# NumPad.net
KiCad netlist of a schematic drawn in EAGLE
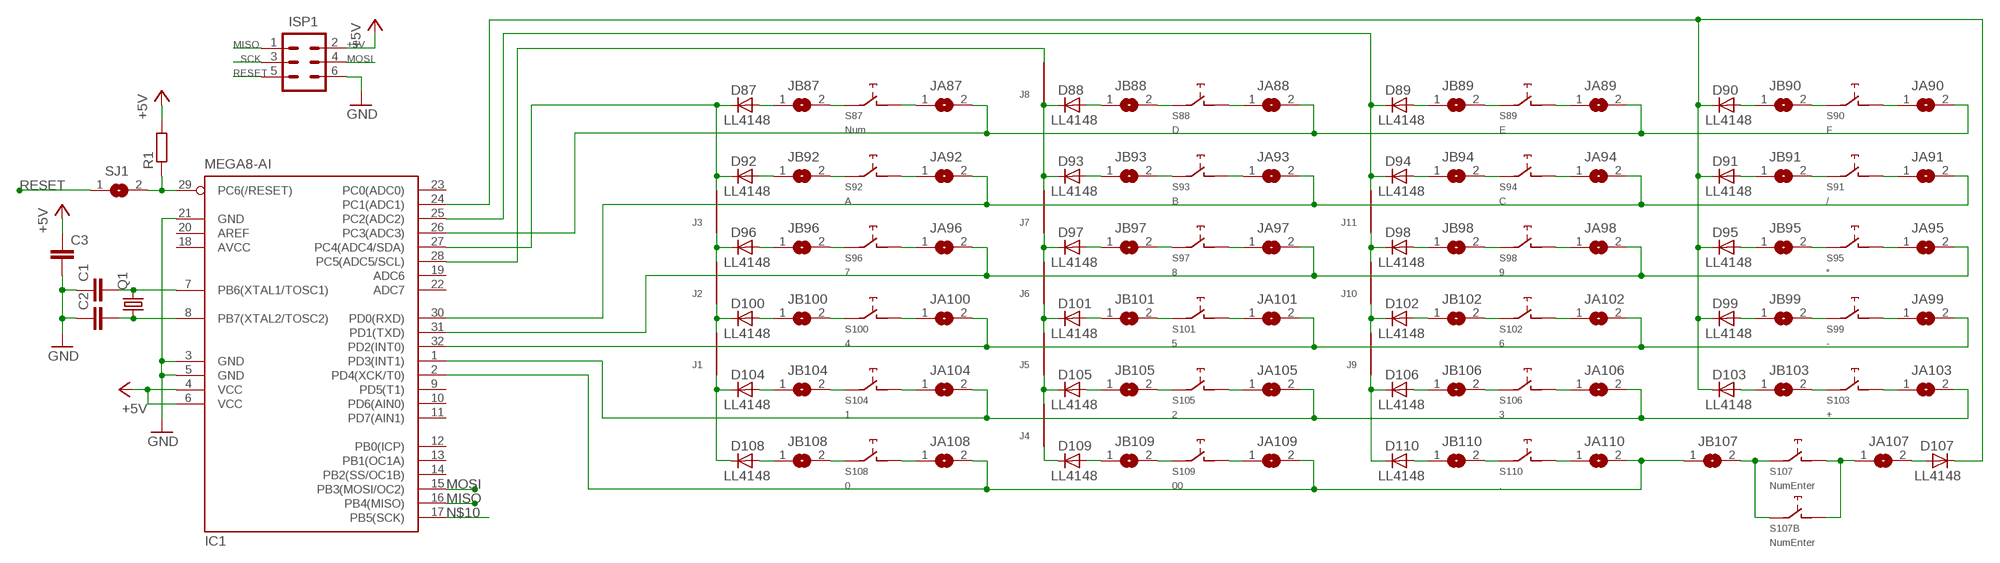
[diagram p0: schematic, sheet 1]

(export (version "E")
  (design (tool "Eeschema 10.0.6"))
  (components
    (comp (ref "C1")
      (value "C-EUC0805")
      (footprint "eagle-import:C0805")
      (libsource (lib "eagle-import") (part "C-EUC0805"))
    )
    (comp (ref "C2")
      (value "C-EUC0805")
      (footprint "eagle-import:C0805")
      (libsource (lib "eagle-import") (part "C-EUC0805"))
    )
    (comp (ref "C3")
      (value "C-EUC0805")
      (footprint "eagle-import:C0805")
      (libsource (lib "eagle-import") (part "C-EUC0805"))
    )
    (comp (ref "D87")
      (value "LL4148")
      (footprint "eagle-import:SOD80C")
      (libsource (lib "eagle-import") (part "LL4148"))
    )
    (comp (ref "D88")
      (value "LL4148")
      (footprint "eagle-import:SOD80C")
      (libsource (lib "eagle-import") (part "LL4148"))
    )
    (comp (ref "D89")
      (value "LL4148")
      (footprint "eagle-import:SOD80C")
      (libsource (lib "eagle-import") (part "LL4148"))
    )
    (comp (ref "D90")
      (value "LL4148")
      (footprint "eagle-import:SOD80C")
      (libsource (lib "eagle-import") (part "LL4148"))
    )
    (comp (ref "D91")
      (value "LL4148")
      (footprint "eagle-import:SOD80C")
      (libsource (lib "eagle-import") (part "LL4148"))
    )
    (comp (ref "D92")
      (value "LL4148")
      (footprint "eagle-import:SOD80C")
      (libsource (lib "eagle-import") (part "LL4148"))
    )
    (comp (ref "D93")
      (value "LL4148")
      (footprint "eagle-import:SOD80C")
      (libsource (lib "eagle-import") (part "LL4148"))
    )
    (comp (ref "D94")
      (value "LL4148")
      (footprint "eagle-import:SOD80C")
      (libsource (lib "eagle-import") (part "LL4148"))
    )
    (comp (ref "D95")
      (value "LL4148")
      (footprint "eagle-import:SOD80C")
      (libsource (lib "eagle-import") (part "LL4148"))
    )
    (comp (ref "D96")
      (value "LL4148")
      (footprint "eagle-import:SOD80C")
      (libsource (lib "eagle-import") (part "LL4148"))
    )
    (comp (ref "D97")
      (value "LL4148")
      (footprint "eagle-import:SOD80C")
      (libsource (lib "eagle-import") (part "LL4148"))
    )
    (comp (ref "D98")
      (value "LL4148")
      (footprint "eagle-import:SOD80C")
      (libsource (lib "eagle-import") (part "LL4148"))
    )
    (comp (ref "D99")
      (value "LL4148")
      (footprint "eagle-import:SOD80C")
      (libsource (lib "eagle-import") (part "LL4148"))
    )
    (comp (ref "D100")
      (value "LL4148")
      (footprint "eagle-import:SOD80C")
      (libsource (lib "eagle-import") (part "LL4148"))
    )
    (comp (ref "D101")
      (value "LL4148")
      (footprint "eagle-import:SOD80C")
      (libsource (lib "eagle-import") (part "LL4148"))
    )
    (comp (ref "D102")
      (value "LL4148")
      (footprint "eagle-import:SOD80C")
      (libsource (lib "eagle-import") (part "LL4148"))
    )
    (comp (ref "D103")
      (value "LL4148")
      (footprint "eagle-import:SOD80C")
      (libsource (lib "eagle-import") (part "LL4148"))
    )
    (comp (ref "D104")
      (value "LL4148")
      (footprint "eagle-import:SOD80C")
      (libsource (lib "eagle-import") (part "LL4148"))
    )
    (comp (ref "D105")
      (value "LL4148")
      (footprint "eagle-import:SOD80C")
      (libsource (lib "eagle-import") (part "LL4148"))
    )
    (comp (ref "D106")
      (value "LL4148")
      (footprint "eagle-import:SOD80C")
      (libsource (lib "eagle-import") (part "LL4148"))
    )
    (comp (ref "D107")
      (value "LL4148")
      (footprint "eagle-import:SOD80C")
      (libsource (lib "eagle-import") (part "LL4148"))
    )
    (comp (ref "D108")
      (value "LL4148")
      (footprint "eagle-import:SOD80C")
      (libsource (lib "eagle-import") (part "LL4148"))
    )
    (comp (ref "D109")
      (value "LL4148")
      (footprint "eagle-import:SOD80C")
      (libsource (lib "eagle-import") (part "LL4148"))
    )
    (comp (ref "D110")
      (value "LL4148")
      (footprint "eagle-import:SOD80C")
      (libsource (lib "eagle-import") (part "LL4148"))
    )
    (comp (ref "IC1")
      (value "MEGA8-AI")
      (footprint "eagle-import:TQFP32-08")
      (fields (field (name "MPN") "ATMEGA8-16AU"))
      (libsource (lib "eagle-import") (part "MEGA8-AI"))
    )
    (comp (ref "ISP1")
      (value "MA03-2")
      (footprint "eagle-import:MA03-2")
      (libsource (lib "eagle-import") (part "MA03-2"))
    )
    (comp (ref "J1")
      (value "J")
      (footprint "eagle-import:R1206W")
      (libsource (lib "eagle-import") (part "J"))
    )
    (comp (ref "J2")
      (value "J")
      (footprint "eagle-import:R1206W")
      (libsource (lib "eagle-import") (part "J"))
    )
    (comp (ref "J3")
      (value "J")
      (footprint "eagle-import:R1206W")
      (libsource (lib "eagle-import") (part "J"))
    )
    (comp (ref "J4")
      (value "J")
      (footprint "eagle-import:R1206W")
      (libsource (lib "eagle-import") (part "J"))
    )
    (comp (ref "J5")
      (value "J")
      (footprint "eagle-import:R1206W")
      (libsource (lib "eagle-import") (part "J"))
    )
    (comp (ref "J6")
      (value "J")
      (footprint "eagle-import:R1206W")
      (libsource (lib "eagle-import") (part "J"))
    )
    (comp (ref "J7")
      (value "J")
      (footprint "eagle-import:R1206W")
      (libsource (lib "eagle-import") (part "J"))
    )
    (comp (ref "J8")
      (value "J")
      (footprint "eagle-import:R1206W")
      (libsource (lib "eagle-import") (part "J"))
    )
    (comp (ref "J9")
      (value "J")
      (footprint "eagle-import:R1206W")
      (libsource (lib "eagle-import") (part "J"))
    )
    (comp (ref "J10")
      (value "J")
      (footprint "eagle-import:R1206W")
      (libsource (lib "eagle-import") (part "J"))
    )
    (comp (ref "J11")
      (value "J")
      (footprint "eagle-import:R1206W")
      (libsource (lib "eagle-import") (part "J"))
    )
    (comp (ref "JA87")
      (value "SJ")
      (footprint "eagle-import:SJ")
      (libsource (lib "eagle-import") (part "SJ"))
    )
    (comp (ref "JA88")
      (value "SJ")
      (footprint "eagle-import:SJ")
      (libsource (lib "eagle-import") (part "SJ"))
    )
    (comp (ref "JA89")
      (value "SJ")
      (footprint "eagle-import:SJ")
      (libsource (lib "eagle-import") (part "SJ"))
    )
    (comp (ref "JA90")
      (value "SJ")
      (footprint "eagle-import:SJ")
      (libsource (lib "eagle-import") (part "SJ"))
    )
    (comp (ref "JA91")
      (value "SJ")
      (footprint "eagle-import:SJ")
      (libsource (lib "eagle-import") (part "SJ"))
    )
    (comp (ref "JA92")
      (value "SJ")
      (footprint "eagle-import:SJ")
      (libsource (lib "eagle-import") (part "SJ"))
    )
    (comp (ref "JA93")
      (value "SJ")
      (footprint "eagle-import:SJ")
      (libsource (lib "eagle-import") (part "SJ"))
    )
    (comp (ref "JA94")
      (value "SJ")
      (footprint "eagle-import:SJ")
      (libsource (lib "eagle-import") (part "SJ"))
    )
    (comp (ref "JA95")
      (value "SJ")
      (footprint "eagle-import:SJ")
      (libsource (lib "eagle-import") (part "SJ"))
    )
    (comp (ref "JA96")
      (value "SJ")
      (footprint "eagle-import:SJ")
      (libsource (lib "eagle-import") (part "SJ"))
    )
    (comp (ref "JA97")
      (value "SJ")
      (footprint "eagle-import:SJ")
      (libsource (lib "eagle-import") (part "SJ"))
    )
    (comp (ref "JA98")
      (value "SJ")
      (footprint "eagle-import:SJ")
      (libsource (lib "eagle-import") (part "SJ"))
    )
    (comp (ref "JA99")
      (value "SJ")
      (footprint "eagle-import:SJ")
      (libsource (lib "eagle-import") (part "SJ"))
    )
    (comp (ref "JA100")
      (value "SJ")
      (footprint "eagle-import:SJ")
      (libsource (lib "eagle-import") (part "SJ"))
    )
    (comp (ref "JA101")
      (value "SJ")
      (footprint "eagle-import:SJ")
      (libsource (lib "eagle-import") (part "SJ"))
    )
    (comp (ref "JA102")
      (value "SJ")
      (footprint "eagle-import:SJ")
      (libsource (lib "eagle-import") (part "SJ"))
    )
    (comp (ref "JA103")
      (value "SJ")
      (footprint "eagle-import:SJ")
      (libsource (lib "eagle-import") (part "SJ"))
    )
    (comp (ref "JA104")
      (value "SJ")
      (footprint "eagle-import:SJ")
      (libsource (lib "eagle-import") (part "SJ"))
    )
    (comp (ref "JA105")
      (value "SJ")
      (footprint "eagle-import:SJ")
      (libsource (lib "eagle-import") (part "SJ"))
    )
    (comp (ref "JA106")
      (value "SJ")
      (footprint "eagle-import:SJ")
      (libsource (lib "eagle-import") (part "SJ"))
    )
    (comp (ref "JA107")
      (value "SJ")
      (footprint "eagle-import:SJ")
      (libsource (lib "eagle-import") (part "SJ"))
    )
    (comp (ref "JA108")
      (value "SJ")
      (footprint "eagle-import:SJ")
      (libsource (lib "eagle-import") (part "SJ"))
    )
    (comp (ref "JA109")
      (value "SJ")
      (footprint "eagle-import:SJ")
      (libsource (lib "eagle-import") (part "SJ"))
    )
    (comp (ref "JA110")
      (value "SJ")
      (footprint "eagle-import:SJ")
      (libsource (lib "eagle-import") (part "SJ"))
    )
    (comp (ref "JB87")
      (value "SJ")
      (footprint "eagle-import:SJ")
      (libsource (lib "eagle-import") (part "SJ"))
    )
    (comp (ref "JB88")
      (value "SJ")
      (footprint "eagle-import:SJ")
      (libsource (lib "eagle-import") (part "SJ"))
    )
    (comp (ref "JB89")
      (value "SJ")
      (footprint "eagle-import:SJ")
      (libsource (lib "eagle-import") (part "SJ"))
    )
    (comp (ref "JB90")
      (value "SJ")
      (footprint "eagle-import:SJ")
      (libsource (lib "eagle-import") (part "SJ"))
    )
    (comp (ref "JB91")
      (value "SJ")
      (footprint "eagle-import:SJ")
      (libsource (lib "eagle-import") (part "SJ"))
    )
    (comp (ref "JB92")
      (value "SJ")
      (footprint "eagle-import:SJ")
      (libsource (lib "eagle-import") (part "SJ"))
    )
    (comp (ref "JB93")
      (value "SJ")
      (footprint "eagle-import:SJ")
      (libsource (lib "eagle-import") (part "SJ"))
    )
    (comp (ref "JB94")
      (value "SJ")
      (footprint "eagle-import:SJ")
      (libsource (lib "eagle-import") (part "SJ"))
    )
    (comp (ref "JB95")
      (value "SJ")
      (footprint "eagle-import:SJ")
      (libsource (lib "eagle-import") (part "SJ"))
    )
    (comp (ref "JB96")
      (value "SJ")
      (footprint "eagle-import:SJ")
      (libsource (lib "eagle-import") (part "SJ"))
    )
    (comp (ref "JB97")
      (value "SJ")
      (footprint "eagle-import:SJ")
      (libsource (lib "eagle-import") (part "SJ"))
    )
    (comp (ref "JB98")
      (value "SJ")
      (footprint "eagle-import:SJ")
      (libsource (lib "eagle-import") (part "SJ"))
    )
    (comp (ref "JB99")
      (value "SJ")
      (footprint "eagle-import:SJ")
      (libsource (lib "eagle-import") (part "SJ"))
    )
    (comp (ref "JB100")
      (value "SJ")
      (footprint "eagle-import:SJ")
      (libsource (lib "eagle-import") (part "SJ"))
    )
    (comp (ref "JB101")
      (value "SJ")
      (footprint "eagle-import:SJ")
      (libsource (lib "eagle-import") (part "SJ"))
    )
    (comp (ref "JB102")
      (value "SJ")
      (footprint "eagle-import:SJ")
      (libsource (lib "eagle-import") (part "SJ"))
    )
    (comp (ref "JB103")
      (value "SJ")
      (footprint "eagle-import:SJ")
      (libsource (lib "eagle-import") (part "SJ"))
    )
    (comp (ref "JB104")
      (value "SJ")
      (footprint "eagle-import:SJ")
      (libsource (lib "eagle-import") (part "SJ"))
    )
    (comp (ref "JB105")
      (value "SJ")
      (footprint "eagle-import:SJ")
      (libsource (lib "eagle-import") (part "SJ"))
    )
    (comp (ref "JB106")
      (value "SJ")
      (footprint "eagle-import:SJ")
      (libsource (lib "eagle-import") (part "SJ"))
    )
    (comp (ref "JB107")
      (value "SJ")
      (footprint "eagle-import:SJ")
      (libsource (lib "eagle-import") (part "SJ"))
    )
    (comp (ref "JB108")
      (value "SJ")
      (footprint "eagle-import:SJ")
      (libsource (lib "eagle-import") (part "SJ"))
    )
    (comp (ref "JB109")
      (value "SJ")
      (footprint "eagle-import:SJ")
      (libsource (lib "eagle-import") (part "SJ"))
    )
    (comp (ref "JB110")
      (value "SJ")
      (footprint "eagle-import:SJ")
      (libsource (lib "eagle-import") (part "SJ"))
    )
    (comp (ref "Q1")
      (value "CRYSTALHC49S")
      (footprint "eagle-import:HC49_S")
      (libsource (lib "eagle-import") (part "CRYSTALHC49S"))
    )
    (comp (ref "R1")
      (value "R-EU_R0805")
      (footprint "eagle-import:R0805")
      (libsource (lib "eagle-import") (part "R-EU_R0805"))
    )
    (comp (ref "S87")
      (value "Num")
      (footprint "eagle-import:CHERRY-MX-4P")
      (libsource (lib "eagle-import") (part "CHERRY-MX-4P"))
    )
    (comp (ref "S88")
      (value "D")
      (footprint "eagle-import:CHERRY-MX-4P")
      (libsource (lib "eagle-import") (part "CHERRY-MX-4P"))
    )
    (comp (ref "S89")
      (value "E")
      (footprint "eagle-import:CHERRY-MX-4P")
      (libsource (lib "eagle-import") (part "CHERRY-MX-4P"))
    )
    (comp (ref "S90")
      (value "F")
      (footprint "eagle-import:CHERRY-MX-4P")
      (libsource (lib "eagle-import") (part "CHERRY-MX-4P"))
    )
    (comp (ref "S91")
      (value "/")
      (footprint "eagle-import:CHERRY-MX-4P")
      (libsource (lib "eagle-import") (part "CHERRY-MX-4P"))
    )
    (comp (ref "S92")
      (value "A")
      (footprint "eagle-import:CHERRY-MX-4P")
      (libsource (lib "eagle-import") (part "CHERRY-MX-4P"))
    )
    (comp (ref "S93")
      (value "B")
      (footprint "eagle-import:CHERRY-MX-4P")
      (libsource (lib "eagle-import") (part "CHERRY-MX-4P"))
    )
    (comp (ref "S94")
      (value "C")
      (footprint "eagle-import:CHERRY-MX-4P")
      (libsource (lib "eagle-import") (part "CHERRY-MX-4P"))
    )
    (comp (ref "S95")
      (value "*")
      (footprint "eagle-import:CHERRY-MX-4P")
      (libsource (lib "eagle-import") (part "CHERRY-MX-4P"))
    )
    (comp (ref "S96")
      (value "7")
      (footprint "eagle-import:CHERRY-MX-4P")
      (libsource (lib "eagle-import") (part "CHERRY-MX-4P"))
    )
    (comp (ref "S97")
      (value "8")
      (footprint "eagle-import:CHERRY-MX-4P")
      (libsource (lib "eagle-import") (part "CHERRY-MX-4P"))
    )
    (comp (ref "S98")
      (value "9")
      (footprint "eagle-import:CHERRY-MX-4P")
      (libsource (lib "eagle-import") (part "CHERRY-MX-4P"))
    )
    (comp (ref "S99")
      (value "-")
      (footprint "eagle-import:CHERRY-MX-4P")
      (libsource (lib "eagle-import") (part "CHERRY-MX-4P"))
    )
    (comp (ref "S100")
      (value "4")
      (footprint "eagle-import:CHERRY-MX-4P")
      (libsource (lib "eagle-import") (part "CHERRY-MX-4P"))
    )
    (comp (ref "S101")
      (value "5")
      (footprint "eagle-import:CHERRY-MX-4P")
      (libsource (lib "eagle-import") (part "CHERRY-MX-4P"))
    )
    (comp (ref "S102")
      (value "6")
      (footprint "eagle-import:CHERRY-MX-4P")
      (libsource (lib "eagle-import") (part "CHERRY-MX-4P"))
    )
    (comp (ref "S103")
      (value "+")
      (footprint "eagle-import:CHERRY-MX-4P")
      (libsource (lib "eagle-import") (part "CHERRY-MX-4P"))
    )
    (comp (ref "S104")
      (value "1")
      (footprint "eagle-import:CHERRY-MX-4P")
      (libsource (lib "eagle-import") (part "CHERRY-MX-4P"))
    )
    (comp (ref "S105")
      (value "2")
      (footprint "eagle-import:CHERRY-MX-4P")
      (libsource (lib "eagle-import") (part "CHERRY-MX-4P"))
    )
    (comp (ref "S106")
      (value "3")
      (footprint "eagle-import:CHERRY-MX-4P")
      (libsource (lib "eagle-import") (part "CHERRY-MX-4P"))
    )
    (comp (ref "S107")
      (value "NumEnter")
      (footprint "eagle-import:CHERRY-MX-4P")
      (libsource (lib "eagle-import") (part "CHERRY-MX-4P"))
    )
    (comp (ref "S107B")
      (value "NumEnter")
      (footprint "eagle-import:CHERRY-MX")
      (libsource (lib "eagle-import") (part "CHERRY-MX"))
    )
    (comp (ref "S108")
      (value "0")
      (footprint "eagle-import:CHERRY-MX-4P")
      (libsource (lib "eagle-import") (part "CHERRY-MX-4P"))
    )
    (comp (ref "S109")
      (value "00")
      (footprint "eagle-import:CHERRY-MX-4P")
      (libsource (lib "eagle-import") (part "CHERRY-MX-4P"))
    )
    (comp (ref "S110")
      (value ".")
      (footprint "eagle-import:CHERRY-MX-4P")
      (libsource (lib "eagle-import") (part "CHERRY-MX-4P"))
    )
    (comp (ref "SJ1") (value "SJ") (footprint "eagle-import:SJ") (libsource (lib "eagle-import") (part "SJ")))
  )
  (nets
    (net (code "1") (name "+5V") (class "Default")
      (node (ref "C3") (pin "1") (pinfunction "1_1") (pintype "passive"))
      (node (ref "IC1") (pin "4") (pinfunction "VCC_4") (pintype "power_in"))
      (node (ref "IC1") (pin "6") (pinfunction "VCC_6") (pintype "power_in"))
      (node (ref "ISP1") (pin "2") (pinfunction "2_2") (pintype "passive"))
      (node (ref "R1") (pin "2") (pinfunction "2_2") (pintype "passive"))
    )
    (net (code "2") (name "/AVCC") (class "Default")
      (node (ref "IC1") (pin "18") (pinfunction "AVCC_18") (pintype "power_in"))
    )
    (net (code "3") (name "/MISO") (class "Default")
      (node (ref "IC1") (pin "16") (pinfunction "PB4(MISO)_16") (pintype "bidirectional"))
      (node (ref "ISP1") (pin "1") (pinfunction "1_1") (pintype "passive"))
    )
    (net (code "4") (name "/MOSI") (class "Default")
      (node (ref "IC1") (pin "15") (pinfunction "PB3(MOSI/OC2)_15") (pintype "bidirectional"))
      (node (ref "ISP1") (pin "4") (pinfunction "4_4") (pintype "passive"))
    )
    (net (code "5") (name "/N$10") (class "Default")
      (node (ref "IC1") (pin "17") (pinfunction "PB5(SCK)_17") (pintype "bidirectional"))
    )
    (net (code "6") (name "/RESET") (class "Default")
      (node (ref "ISP1") (pin "5") (pinfunction "5_5") (pintype "passive"))
      (node (ref "SJ1") (pin "1") (pinfunction "1_1") (pintype "passive"))
    )
    (net (code "7") (name "/SCK") (class "Default")
      (node (ref "D103") (pin "C") (pinfunction "C_C") (pintype "passive"))
      (node (ref "D107") (pin "C") (pinfunction "C_C") (pintype "passive"))
      (node (ref "D90") (pin "C") (pinfunction "C_C") (pintype "passive"))
      (node (ref "D91") (pin "C") (pinfunction "C_C") (pintype "passive"))
      (node (ref "D95") (pin "C") (pinfunction "C_C") (pintype "passive"))
      (node (ref "D99") (pin "C") (pinfunction "C_C") (pintype "passive"))
      (node (ref "IC1") (pin "24") (pinfunction "PC1(ADC1)_24") (pintype "bidirectional"))
      (node (ref "ISP1") (pin "3") (pinfunction "3_3") (pintype "passive"))
    )
    (net (code "8") (name "GND") (class "Default")
      (node (ref "C1") (pin "1") (pinfunction "1_1") (pintype "passive"))
      (node (ref "C2") (pin "1") (pinfunction "1_1") (pintype "passive"))
      (node (ref "C3") (pin "2") (pinfunction "2_2") (pintype "passive"))
      (node (ref "IC1") (pin "21") (pinfunction "GND_21") (pintype "power_in"))
      (node (ref "IC1") (pin "3") (pinfunction "GND_3") (pintype "power_in"))
      (node (ref "IC1") (pin "5") (pinfunction "GND_5") (pintype "power_in"))
      (node (ref "ISP1") (pin "6") (pinfunction "6_6") (pintype "passive"))
    )
    (net (code "9") (name "Net-(D87-PadA)") (class "Default")
      (node (ref "D87") (pin "A") (pinfunction "A_A") (pintype "passive"))
      (node (ref "JB87") (pin "1") (pinfunction "1_1") (pintype "passive"))
    )
    (net (code "10") (name "Net-(D88-PadA)") (class "Default")
      (node (ref "D88") (pin "A") (pinfunction "A_A") (pintype "passive"))
      (node (ref "JB88") (pin "1") (pinfunction "1_1") (pintype "passive"))
    )
    (net (code "11") (name "Net-(D89-PadA)") (class "Default")
      (node (ref "D89") (pin "A") (pinfunction "A_A") (pintype "passive"))
      (node (ref "JB89") (pin "1") (pinfunction "1_1") (pintype "passive"))
    )
    (net (code "12") (name "Net-(D90-PadA)") (class "Default")
      (node (ref "D90") (pin "A") (pinfunction "A_A") (pintype "passive"))
      (node (ref "JB90") (pin "1") (pinfunction "1_1") (pintype "passive"))
    )
    (net (code "13") (name "Net-(D91-PadA)") (class "Default")
      (node (ref "D91") (pin "A") (pinfunction "A_A") (pintype "passive"))
      (node (ref "JB91") (pin "1") (pinfunction "1_1") (pintype "passive"))
    )
    (net (code "14") (name "Net-(D92-PadA)") (class "Default")
      (node (ref "D92") (pin "A") (pinfunction "A_A") (pintype "passive"))
      (node (ref "JB92") (pin "1") (pinfunction "1_1") (pintype "passive"))
    )
    (net (code "15") (name "Net-(D93-PadA)") (class "Default")
      (node (ref "D93") (pin "A") (pinfunction "A_A") (pintype "passive"))
      (node (ref "JB93") (pin "1") (pinfunction "1_1") (pintype "passive"))
    )
    (net (code "16") (name "Net-(D94-PadA)") (class "Default")
      (node (ref "D94") (pin "A") (pinfunction "A_A") (pintype "passive"))
      (node (ref "JB94") (pin "1") (pinfunction "1_1") (pintype "passive"))
    )
    (net (code "17") (name "Net-(D95-PadA)") (class "Default")
      (node (ref "D95") (pin "A") (pinfunction "A_A") (pintype "passive"))
      (node (ref "JB95") (pin "1") (pinfunction "1_1") (pintype "passive"))
    )
    (net (code "18") (name "Net-(D96-PadA)") (class "Default")
      (node (ref "D96") (pin "A") (pinfunction "A_A") (pintype "passive"))
      (node (ref "JB96") (pin "1") (pinfunction "1_1") (pintype "passive"))
    )
    (net (code "19") (name "Net-(D97-PadA)") (class "Default")
      (node (ref "D97") (pin "A") (pinfunction "A_A") (pintype "passive"))
      (node (ref "JB97") (pin "1") (pinfunction "1_1") (pintype "passive"))
    )
    (net (code "20") (name "Net-(D98-PadA)") (class "Default")
      (node (ref "D98") (pin "A") (pinfunction "A_A") (pintype "passive"))
      (node (ref "JB98") (pin "1") (pinfunction "1_1") (pintype "passive"))
    )
    (net (code "21") (name "Net-(D99-PadA)") (class "Default")
      (node (ref "D99") (pin "A") (pinfunction "A_A") (pintype "passive"))
      (node (ref "JB99") (pin "1") (pinfunction "1_1") (pintype "passive"))
    )
    (net (code "22") (name "Net-(D100-PadA)") (class "Default")
      (node (ref "D100") (pin "A") (pinfunction "A_A") (pintype "passive"))
      (node (ref "JB100") (pin "1") (pinfunction "1_1") (pintype "passive"))
    )
    (net (code "23") (name "Net-(D101-PadA)") (class "Default")
      (node (ref "D101") (pin "A") (pinfunction "A_A") (pintype "passive"))
      (node (ref "JB101") (pin "1") (pinfunction "1_1") (pintype "passive"))
    )
    (net (code "24") (name "Net-(D102-PadA)") (class "Default")
      (node (ref "D102") (pin "A") (pinfunction "A_A") (pintype "passive"))
      (node (ref "JB102") (pin "1") (pinfunction "1_1") (pintype "passive"))
    )
    (net (code "25") (name "Net-(D103-PadA)") (class "Default")
      (node (ref "D103") (pin "A") (pinfunction "A_A") (pintype "passive"))
      (node (ref "JB103") (pin "1") (pinfunction "1_1") (pintype "passive"))
    )
    (net (code "26") (name "Net-(D104-PadA)") (class "Default")
      (node (ref "D104") (pin "A") (pinfunction "A_A") (pintype "passive"))
      (node (ref "JB104") (pin "1") (pinfunction "1_1") (pintype "passive"))
    )
    (net (code "27") (name "Net-(D105-PadA)") (class "Default")
      (node (ref "D105") (pin "A") (pinfunction "A_A") (pintype "passive"))
      (node (ref "JB105") (pin "1") (pinfunction "1_1") (pintype "passive"))
    )
    (net (code "28") (name "Net-(D106-PadA)") (class "Default")
      (node (ref "D106") (pin "A") (pinfunction "A_A") (pintype "passive"))
      (node (ref "JB106") (pin "1") (pinfunction "1_1") (pintype "passive"))
    )
    (net (code "29") (name "Net-(D107-PadA)") (class "Default")
      (node (ref "D107") (pin "A") (pinfunction "A_A") (pintype "passive"))
      (node (ref "JA107") (pin "2") (pinfunction "2_2") (pintype "passive"))
    )
    (net (code "30") (name "Net-(D108-PadA)") (class "Default")
      (node (ref "D108") (pin "A") (pinfunction "A_A") (pintype "passive"))
      (node (ref "JB108") (pin "1") (pinfunction "1_1") (pintype "passive"))
    )
    (net (code "31") (name "Net-(D109-PadA)") (class "Default")
      (node (ref "D109") (pin "A") (pinfunction "A_A") (pintype "passive"))
      (node (ref "JB109") (pin "1") (pinfunction "1_1") (pintype "passive"))
    )
    (net (code "32") (name "Net-(D110-PadA)") (class "Default")
      (node (ref "D110") (pin "A") (pinfunction "A_A") (pintype "passive"))
      (node (ref "JB110") (pin "1") (pinfunction "1_1") (pintype "passive"))
    )
    (net (code "33") (name "Net-(IC1-PB6(XTAL1{slash}TOSC1))") (class "Default")
      (node (ref "C1") (pin "2") (pinfunction "2_2") (pintype "passive"))
      (node (ref "IC1") (pin "7") (pinfunction "PB6(XTAL1/TOSC1)_7") (pintype "bidirectional"))
      (node (ref "Q1") (pin "2") (pinfunction "2_2") (pintype "passive"))
    )
    (net (code "34") (name "Net-(IC1-PB7(XTAL2{slash}TOSC2))") (class "Default")
      (node (ref "C2") (pin "2") (pinfunction "2_2") (pintype "passive"))
      (node (ref "IC1") (pin "8") (pinfunction "PB7(XTAL2/TOSC2)_8") (pintype "bidirectional"))
      (node (ref "Q1") (pin "1") (pinfunction "1_1") (pintype "passive"))
    )
    (net (code "35") (name "Net-(IC1-PC2(ADC2))") (class "Default")
      (node (ref "D89") (pin "C") (pinfunction "C_C") (pintype "passive"))
      (node (ref "D94") (pin "C") (pinfunction "C_C") (pintype "passive"))
      (node (ref "IC1") (pin "25") (pinfunction "PC2(ADC2)_25") (pintype "bidirectional"))
      (node (ref "J11") (pin "1") (pinfunction "P$1_1") (pintype "bidirectional"))
    )
    (net (code "36") (name "Net-(IC1-PC3(ADC3))") (class "Default")
      (node (ref "IC1") (pin "26") (pinfunction "PC3(ADC3)_26") (pintype "bidirectional"))
      (node (ref "JA87") (pin "2") (pinfunction "2_2") (pintype "passive"))
      (node (ref "JA88") (pin "2") (pinfunction "2_2") (pintype "passive"))
      (node (ref "JA89") (pin "2") (pinfunction "2_2") (pintype "passive"))
      (node (ref "JA90") (pin "2") (pinfunction "2_2") (pintype "passive"))
    )
    (net (code "37") (name "Net-(IC1-PC4(ADC4{slash}SDA))") (class "Default")
      (node (ref "D87") (pin "C") (pinfunction "C_C") (pintype "passive"))
      (node (ref "D92") (pin "C") (pinfunction "C_C") (pintype "passive"))
      (node (ref "IC1") (pin "27") (pinfunction "PC4(ADC4/SDA)_27") (pintype "bidirectional"))
      (node (ref "J3") (pin "1") (pinfunction "P$1_1") (pintype "bidirectional"))
    )
    (net (code "38") (name "Net-(IC1-PC5(ADC5{slash}SCL))") (class "Default")
      (node (ref "IC1") (pin "28") (pinfunction "PC5(ADC5/SCL)_28") (pintype "bidirectional"))
      (node (ref "J8") (pin "1") (pinfunction "P$1_1") (pintype "bidirectional"))
    )
    (net (code "39") (name "Net-(IC1-PC6({slash}RESET))") (class "Default")
      (node (ref "IC1") (pin "29") (pinfunction "PC6(/RESET)_29") (pintype "bidirectional"))
      (node (ref "R1") (pin "1") (pinfunction "1_1") (pintype "passive"))
      (node (ref "SJ1") (pin "2") (pinfunction "2_2") (pintype "passive"))
    )
    (net (code "40") (name "Net-(IC1-PD0(RXD))") (class "Default")
      (node (ref "IC1") (pin "30") (pinfunction "PD0(RXD)_30") (pintype "bidirectional"))
      (node (ref "JA91") (pin "2") (pinfunction "2_2") (pintype "passive"))
      (node (ref "JA92") (pin "2") (pinfunction "2_2") (pintype "passive"))
      (node (ref "JA93") (pin "2") (pinfunction "2_2") (pintype "passive"))
      (node (ref "JA94") (pin "2") (pinfunction "2_2") (pintype "passive"))
    )
    (net (code "41") (name "Net-(IC1-PD1(TXD))") (class "Default")
      (node (ref "IC1") (pin "31") (pinfunction "PD1(TXD)_31") (pintype "bidirectional"))
      (node (ref "JA95") (pin "2") (pinfunction "2_2") (pintype "passive"))
      (node (ref "JA96") (pin "2") (pinfunction "2_2") (pintype "passive"))
      (node (ref "JA97") (pin "2") (pinfunction "2_2") (pintype "passive"))
      (node (ref "JA98") (pin "2") (pinfunction "2_2") (pintype "passive"))
    )
    (net (code "42") (name "Net-(IC1-PD2(INT0))") (class "Default")
      (node (ref "IC1") (pin "32") (pinfunction "PD2(INT0)_32") (pintype "bidirectional"))
      (node (ref "JA100") (pin "2") (pinfunction "2_2") (pintype "passive"))
      (node (ref "JA101") (pin "2") (pinfunction "2_2") (pintype "passive"))
      (node (ref "JA102") (pin "2") (pinfunction "2_2") (pintype "passive"))
      (node (ref "JA99") (pin "2") (pinfunction "2_2") (pintype "passive"))
    )
    (net (code "43") (name "Net-(IC1-PD3(INT1))") (class "Default")
      (node (ref "IC1") (pin "1") (pinfunction "PD3(INT1)_1") (pintype "bidirectional"))
      (node (ref "JA103") (pin "2") (pinfunction "2_2") (pintype "passive"))
      (node (ref "JA104") (pin "2") (pinfunction "2_2") (pintype "passive"))
      (node (ref "JA105") (pin "2") (pinfunction "2_2") (pintype "passive"))
      (node (ref "JA106") (pin "2") (pinfunction "2_2") (pintype "passive"))
    )
    (net (code "44") (name "Net-(IC1-PD4(XCK{slash}T0))") (class "Default")
      (node (ref "IC1") (pin "2") (pinfunction "PD4(XCK/T0)_2") (pintype "bidirectional"))
      (node (ref "JA108") (pin "2") (pinfunction "2_2") (pintype "passive"))
      (node (ref "JA109") (pin "2") (pinfunction "2_2") (pintype "passive"))
      (node (ref "JA110") (pin "2") (pinfunction "2_2") (pintype "passive"))
      (node (ref "JB107") (pin "1") (pinfunction "1_1") (pintype "passive"))
    )
    (net (code "45") (name "Net-(J1-P$1)") (class "Default")
      (node (ref "D100") (pin "C") (pinfunction "C_C") (pintype "passive"))
      (node (ref "J1") (pin "1") (pinfunction "P$1_1") (pintype "bidirectional"))
      (node (ref "J2") (pin "2") (pinfunction "P$2_2") (pintype "bidirectional"))
    )
    (net (code "46") (name "Net-(J1-P$2)") (class "Default")
      (node (ref "D104") (pin "C") (pinfunction "C_C") (pintype "passive"))
      (node (ref "D108") (pin "C") (pinfunction "C_C") (pintype "passive"))
      (node (ref "J1") (pin "2") (pinfunction "P$2_2") (pintype "bidirectional"))
    )
    (net (code "47") (name "Net-(J2-P$1)") (class "Default")
      (node (ref "D96") (pin "C") (pinfunction "C_C") (pintype "passive"))
      (node (ref "J2") (pin "1") (pinfunction "P$1_1") (pintype "bidirectional"))
      (node (ref "J3") (pin "2") (pinfunction "P$2_2") (pintype "bidirectional"))
    )
    (net (code "48") (name "Net-(J4-P$1)") (class "Default")
      (node (ref "D105") (pin "C") (pinfunction "C_C") (pintype "passive"))
      (node (ref "J4") (pin "1") (pinfunction "P$1_1") (pintype "bidirectional"))
      (node (ref "J5") (pin "2") (pinfunction "P$2_2") (pintype "bidirectional"))
    )
    (net (code "49") (name "Net-(J4-P$2)") (class "Default")
      (node (ref "D109") (pin "C") (pinfunction "C_C") (pintype "passive"))
      (node (ref "J4") (pin "2") (pinfunction "P$2_2") (pintype "bidirectional"))
    )
    (net (code "50") (name "Net-(J5-P$1)") (class "Default")
      (node (ref "D101") (pin "C") (pinfunction "C_C") (pintype "passive"))
      (node (ref "J5") (pin "1") (pinfunction "P$1_1") (pintype "bidirectional"))
      (node (ref "J6") (pin "2") (pinfunction "P$2_2") (pintype "bidirectional"))
    )
    (net (code "51") (name "Net-(J6-P$1)") (class "Default")
      (node (ref "D97") (pin "C") (pinfunction "C_C") (pintype "passive"))
      (node (ref "J6") (pin "1") (pinfunction "P$1_1") (pintype "bidirectional"))
      (node (ref "J7") (pin "2") (pinfunction "P$2_2") (pintype "bidirectional"))
    )
    (net (code "52") (name "Net-(J7-P$1)") (class "Default")
      (node (ref "D88") (pin "C") (pinfunction "C_C") (pintype "passive"))
      (node (ref "D93") (pin "C") (pinfunction "C_C") (pintype "passive"))
      (node (ref "J7") (pin "1") (pinfunction "P$1_1") (pintype "bidirectional"))
      (node (ref "J8") (pin "2") (pinfunction "P$2_2") (pintype "bidirectional"))
    )
    (net (code "53") (name "Net-(J9-P$2)") (class "Default")
      (node (ref "D106") (pin "C") (pinfunction "C_C") (pintype "passive"))
      (node (ref "D110") (pin "C") (pinfunction "C_C") (pintype "passive"))
      (node (ref "J9") (pin "2") (pinfunction "P$2_2") (pintype "bidirectional"))
    )
    (net (code "54") (name "Net-(J10-P$1)") (class "Default")
      (node (ref "D98") (pin "C") (pinfunction "C_C") (pintype "passive"))
      (node (ref "J10") (pin "1") (pinfunction "P$1_1") (pintype "bidirectional"))
      (node (ref "J11") (pin "2") (pinfunction "P$2_2") (pintype "bidirectional"))
    )
    (net (code "55") (name "Net-(J10-P$2)") (class "Default")
      (node (ref "D102") (pin "C") (pinfunction "C_C") (pintype "passive"))
      (node (ref "J10") (pin "2") (pinfunction "P$2_2") (pintype "bidirectional"))
      (node (ref "J9") (pin "1") (pinfunction "P$1_1") (pintype "bidirectional"))
    )
    (net (code "56") (name "Net-(S87A-PIN-1)") (class "Default")
      (node (ref "JB87") (pin "2") (pinfunction "2_2") (pintype "passive"))
      (node (ref "S87") (pin "SW1") (pinfunction "PIN-1_SW1") (pintype "passive"))
    )
    (net (code "57") (name "Net-(S87A-PIN-2)") (class "Default")
      (node (ref "JA87") (pin "1") (pinfunction "1_1") (pintype "passive"))
      (node (ref "S87") (pin "SW2") (pinfunction "PIN-2_SW2") (pintype "passive"))
    )
    (net (code "58") (name "Net-(S88A-PIN-1)") (class "Default")
      (node (ref "JB88") (pin "2") (pinfunction "2_2") (pintype "passive"))
      (node (ref "S88") (pin "SW1") (pinfunction "PIN-1_SW1") (pintype "passive"))
    )
    (net (code "59") (name "Net-(S88A-PIN-2)") (class "Default")
      (node (ref "JA88") (pin "1") (pinfunction "1_1") (pintype "passive"))
      (node (ref "S88") (pin "SW2") (pinfunction "PIN-2_SW2") (pintype "passive"))
    )
    (net (code "60") (name "Net-(S89A-PIN-1)") (class "Default")
      (node (ref "JB89") (pin "2") (pinfunction "2_2") (pintype "passive"))
      (node (ref "S89") (pin "SW1") (pinfunction "PIN-1_SW1") (pintype "passive"))
    )
    (net (code "61") (name "Net-(S89A-PIN-2)") (class "Default")
      (node (ref "JA89") (pin "1") (pinfunction "1_1") (pintype "passive"))
      (node (ref "S89") (pin "SW2") (pinfunction "PIN-2_SW2") (pintype "passive"))
    )
    (net (code "62") (name "Net-(S90A-PIN-1)") (class "Default")
      (node (ref "JB90") (pin "2") (pinfunction "2_2") (pintype "passive"))
      (node (ref "S90") (pin "SW1") (pinfunction "PIN-1_SW1") (pintype "passive"))
    )
    (net (code "63") (name "Net-(S90A-PIN-2)") (class "Default")
      (node (ref "JA90") (pin "1") (pinfunction "1_1") (pintype "passive"))
      (node (ref "S90") (pin "SW2") (pinfunction "PIN-2_SW2") (pintype "passive"))
    )
    (net (code "64") (name "Net-(S91A-PIN-1)") (class "Default")
      (node (ref "JB91") (pin "2") (pinfunction "2_2") (pintype "passive"))
      (node (ref "S91") (pin "SW1") (pinfunction "PIN-1_SW1") (pintype "passive"))
    )
    (net (code "65") (name "Net-(S91A-PIN-2)") (class "Default")
      (node (ref "JA91") (pin "1") (pinfunction "1_1") (pintype "passive"))
      (node (ref "S91") (pin "SW2") (pinfunction "PIN-2_SW2") (pintype "passive"))
    )
    (net (code "66") (name "Net-(S92A-PIN-1)") (class "Default")
      (node (ref "JB92") (pin "2") (pinfunction "2_2") (pintype "passive"))
      (node (ref "S92") (pin "SW1") (pinfunction "PIN-1_SW1") (pintype "passive"))
    )
    (net (code "67") (name "Net-(S92A-PIN-2)") (class "Default")
      (node (ref "JA92") (pin "1") (pinfunction "1_1") (pintype "passive"))
      (node (ref "S92") (pin "SW2") (pinfunction "PIN-2_SW2") (pintype "passive"))
    )
    (net (code "68") (name "Net-(S93A-PIN-1)") (class "Default")
      (node (ref "JB93") (pin "2") (pinfunction "2_2") (pintype "passive"))
      (node (ref "S93") (pin "SW1") (pinfunction "PIN-1_SW1") (pintype "passive"))
    )
    (net (code "69") (name "Net-(S93A-PIN-2)") (class "Default")
      (node (ref "JA93") (pin "1") (pinfunction "1_1") (pintype "passive"))
      (node (ref "S93") (pin "SW2") (pinfunction "PIN-2_SW2") (pintype "passive"))
    )
    (net (code "70") (name "Net-(S94A-PIN-1)") (class "Default")
      (node (ref "JB94") (pin "2") (pinfunction "2_2") (pintype "passive"))
      (node (ref "S94") (pin "SW1") (pinfunction "PIN-1_SW1") (pintype "passive"))
    )
    (net (code "71") (name "Net-(S94A-PIN-2)") (class "Default")
      (node (ref "JA94") (pin "1") (pinfunction "1_1") (pintype "passive"))
      (node (ref "S94") (pin "SW2") (pinfunction "PIN-2_SW2") (pintype "passive"))
    )
    (net (code "72") (name "Net-(S95A-PIN-1)") (class "Default")
      (node (ref "JB95") (pin "2") (pinfunction "2_2") (pintype "passive"))
      (node (ref "S95") (pin "SW1") (pinfunction "PIN-1_SW1") (pintype "passive"))
    )
    (net (code "73") (name "Net-(S95A-PIN-2)") (class "Default")
      (node (ref "JA95") (pin "1") (pinfunction "1_1") (pintype "passive"))
      (node (ref "S95") (pin "SW2") (pinfunction "PIN-2_SW2") (pintype "passive"))
    )
    (net (code "74") (name "Net-(S96A-PIN-1)") (class "Default")
      (node (ref "JB96") (pin "2") (pinfunction "2_2") (pintype "passive"))
      (node (ref "S96") (pin "SW1") (pinfunction "PIN-1_SW1") (pintype "passive"))
    )
    (net (code "75") (name "Net-(S96A-PIN-2)") (class "Default")
      (node (ref "JA96") (pin "1") (pinfunction "1_1") (pintype "passive"))
      (node (ref "S96") (pin "SW2") (pinfunction "PIN-2_SW2") (pintype "passive"))
    )
    (net (code "76") (name "Net-(S97A-PIN-1)") (class "Default")
      (node (ref "JB97") (pin "2") (pinfunction "2_2") (pintype "passive"))
      (node (ref "S97") (pin "SW1") (pinfunction "PIN-1_SW1") (pintype "passive"))
    )
    (net (code "77") (name "Net-(S97A-PIN-2)") (class "Default")
      (node (ref "JA97") (pin "1") (pinfunction "1_1") (pintype "passive"))
      (node (ref "S97") (pin "SW2") (pinfunction "PIN-2_SW2") (pintype "passive"))
    )
    (net (code "78") (name "Net-(S98A-PIN-1)") (class "Default")
      (node (ref "JB98") (pin "2") (pinfunction "2_2") (pintype "passive"))
      (node (ref "S98") (pin "SW1") (pinfunction "PIN-1_SW1") (pintype "passive"))
    )
    (net (code "79") (name "Net-(S98A-PIN-2)") (class "Default")
      (node (ref "JA98") (pin "1") (pinfunction "1_1") (pintype "passive"))
      (node (ref "S98") (pin "SW2") (pinfunction "PIN-2_SW2") (pintype "passive"))
    )
    (net (code "80") (name "Net-(S99A-PIN-1)") (class "Default")
      (node (ref "JB99") (pin "2") (pinfunction "2_2") (pintype "passive"))
      (node (ref "S99") (pin "SW1") (pinfunction "PIN-1_SW1") (pintype "passive"))
    )
    (net (code "81") (name "Net-(S99A-PIN-2)") (class "Default")
      (node (ref "JA99") (pin "1") (pinfunction "1_1") (pintype "passive"))
      (node (ref "S99") (pin "SW2") (pinfunction "PIN-2_SW2") (pintype "passive"))
    )
    (net (code "82") (name "Net-(S100A-PIN-1)") (class "Default")
      (node (ref "JB100") (pin "2") (pinfunction "2_2") (pintype "passive"))
      (node (ref "S100") (pin "SW1") (pinfunction "PIN-1_SW1") (pintype "passive"))
    )
    (net (code "83") (name "Net-(S100A-PIN-2)") (class "Default")
      (node (ref "JA100") (pin "1") (pinfunction "1_1") (pintype "passive"))
      (node (ref "S100") (pin "SW2") (pinfunction "PIN-2_SW2") (pintype "passive"))
    )
    (net (code "84") (name "Net-(S101A-PIN-1)") (class "Default")
      (node (ref "JB101") (pin "2") (pinfunction "2_2") (pintype "passive"))
      (node (ref "S101") (pin "SW1") (pinfunction "PIN-1_SW1") (pintype "passive"))
    )
    (net (code "85") (name "Net-(S101A-PIN-2)") (class "Default")
      (node (ref "JA101") (pin "1") (pinfunction "1_1") (pintype "passive"))
      (node (ref "S101") (pin "SW2") (pinfunction "PIN-2_SW2") (pintype "passive"))
    )
    (net (code "86") (name "Net-(S102A-PIN-1)") (class "Default")
      (node (ref "JB102") (pin "2") (pinfunction "2_2") (pintype "passive"))
      (node (ref "S102") (pin "SW1") (pinfunction "PIN-1_SW1") (pintype "passive"))
    )
    (net (code "87") (name "Net-(S102A-PIN-2)") (class "Default")
      (node (ref "JA102") (pin "1") (pinfunction "1_1") (pintype "passive"))
      (node (ref "S102") (pin "SW2") (pinfunction "PIN-2_SW2") (pintype "passive"))
    )
    (net (code "88") (name "Net-(S103A-PIN-1)") (class "Default")
      (node (ref "JB103") (pin "2") (pinfunction "2_2") (pintype "passive"))
      (node (ref "S103") (pin "SW1") (pinfunction "PIN-1_SW1") (pintype "passive"))
    )
    (net (code "89") (name "Net-(S103A-PIN-2)") (class "Default")
      (node (ref "JA103") (pin "1") (pinfunction "1_1") (pintype "passive"))
      (node (ref "S103") (pin "SW2") (pinfunction "PIN-2_SW2") (pintype "passive"))
    )
    (net (code "90") (name "Net-(S104A-PIN-1)") (class "Default")
      (node (ref "JB104") (pin "2") (pinfunction "2_2") (pintype "passive"))
      (node (ref "S104") (pin "SW1") (pinfunction "PIN-1_SW1") (pintype "passive"))
    )
    (net (code "91") (name "Net-(S104A-PIN-2)") (class "Default")
      (node (ref "JA104") (pin "1") (pinfunction "1_1") (pintype "passive"))
      (node (ref "S104") (pin "SW2") (pinfunction "PIN-2_SW2") (pintype "passive"))
    )
    (net (code "92") (name "Net-(S105A-PIN-1)") (class "Default")
      (node (ref "JB105") (pin "2") (pinfunction "2_2") (pintype "passive"))
      (node (ref "S105") (pin "SW1") (pinfunction "PIN-1_SW1") (pintype "passive"))
    )
    (net (code "93") (name "Net-(S105A-PIN-2)") (class "Default")
      (node (ref "JA105") (pin "1") (pinfunction "1_1") (pintype "passive"))
      (node (ref "S105") (pin "SW2") (pinfunction "PIN-2_SW2") (pintype "passive"))
    )
    (net (code "94") (name "Net-(S106A-PIN-1)") (class "Default")
      (node (ref "JB106") (pin "2") (pinfunction "2_2") (pintype "passive"))
      (node (ref "S106") (pin "SW1") (pinfunction "PIN-1_SW1") (pintype "passive"))
    )
    (net (code "95") (name "Net-(S106A-PIN-2)") (class "Default")
      (node (ref "JA106") (pin "1") (pinfunction "1_1") (pintype "passive"))
      (node (ref "S106") (pin "SW2") (pinfunction "PIN-2_SW2") (pintype "passive"))
    )
    (net (code "96") (name "Net-(S107A-PIN-1)") (class "Default")
      (node (ref "JB107") (pin "2") (pinfunction "2_2") (pintype "passive"))
      (node (ref "S107") (pin "SW1") (pinfunction "PIN-1_SW1") (pintype "passive"))
      (node (ref "S107B") (pin "SW1") (pinfunction "PIN-1_SW1") (pintype "passive"))
    )
    (net (code "97") (name "Net-(S107A-PIN-2)") (class "Default")
      (node (ref "JA107") (pin "1") (pinfunction "1_1") (pintype "passive"))
      (node (ref "S107") (pin "SW2") (pinfunction "PIN-2_SW2") (pintype "passive"))
      (node (ref "S107B") (pin "SW2") (pinfunction "PIN-2_SW2") (pintype "passive"))
    )
    (net (code "98") (name "Net-(S108A-PIN-1)") (class "Default")
      (node (ref "JB108") (pin "2") (pinfunction "2_2") (pintype "passive"))
      (node (ref "S108") (pin "SW1") (pinfunction "PIN-1_SW1") (pintype "passive"))
    )
    (net (code "99") (name "Net-(S108A-PIN-2)") (class "Default")
      (node (ref "JA108") (pin "1") (pinfunction "1_1") (pintype "passive"))
      (node (ref "S108") (pin "SW2") (pinfunction "PIN-2_SW2") (pintype "passive"))
    )
    (net (code "100") (name "Net-(S109A-PIN-1)") (class "Default")
      (node (ref "JB109") (pin "2") (pinfunction "2_2") (pintype "passive"))
      (node (ref "S109") (pin "SW1") (pinfunction "PIN-1_SW1") (pintype "passive"))
    )
    (net (code "101") (name "Net-(S109A-PIN-2)") (class "Default")
      (node (ref "JA109") (pin "1") (pinfunction "1_1") (pintype "passive"))
      (node (ref "S109") (pin "SW2") (pinfunction "PIN-2_SW2") (pintype "passive"))
    )
    (net (code "102") (name "Net-(S110A-PIN-1)") (class "Default")
      (node (ref "JB110") (pin "2") (pinfunction "2_2") (pintype "passive"))
      (node (ref "S110") (pin "SW1") (pinfunction "PIN-1_SW1") (pintype "passive"))
    )
    (net (code "103") (name "Net-(S110A-PIN-2)") (class "Default")
      (node (ref "JA110") (pin "1") (pinfunction "1_1") (pintype "passive"))
      (node (ref "S110") (pin "SW2") (pinfunction "PIN-2_SW2") (pintype "passive"))
    )
    (net (code "104") (name "unconnected-(IC1-ADC6-Pad19)") (class "Default")
      (node (ref "IC1") (pin "19") (pinfunction "ADC6_19") (pintype "bidirectional"))
    )
    (net (code "105") (name "unconnected-(IC1-ADC7-Pad22)") (class "Default")
      (node (ref "IC1") (pin "22") (pinfunction "ADC7_22") (pintype "bidirectional"))
    )
    (net (code "106") (name "unconnected-(IC1-AREF-Pad20)") (class "Default")
      (node (ref "IC1") (pin "20") (pinfunction "AREF_20") (pintype "passive"))
    )
    (net (code "107") (name "unconnected-(IC1-PB0(ICP)-Pad12)") (class "Default")
      (node (ref "IC1") (pin "12") (pinfunction "PB0(ICP)_12") (pintype "bidirectional"))
    )
    (net (code "108") (name "unconnected-(IC1-PB1(OC1A)-Pad13)") (class "Default")
      (node (ref "IC1") (pin "13") (pinfunction "PB1(OC1A)_13") (pintype "bidirectional"))
    )
    (net (code "109") (name "unconnected-(IC1-PB2(SS{slash}OC1B)-Pad14)") (class "Default")
      (node (ref "IC1") (pin "14") (pinfunction "PB2(SS/OC1B)_14") (pintype "bidirectional"))
    )
    (net (code "110") (name "unconnected-(IC1-PC0(ADC0)-Pad23)") (class "Default")
      (node (ref "IC1") (pin "23") (pinfunction "PC0(ADC0)_23") (pintype "bidirectional"))
    )
    (net (code "111") (name "unconnected-(IC1-PD5(T1)-Pad9)") (class "Default")
      (node (ref "IC1") (pin "9") (pinfunction "PD5(T1)_9") (pintype "bidirectional"))
    )
    (net (code "112") (name "unconnected-(IC1-PD6(AIN0)-Pad10)") (class "Default")
      (node (ref "IC1") (pin "10") (pinfunction "PD6(AIN0)_10") (pintype "bidirectional"))
    )
    (net (code "113") (name "unconnected-(IC1-PD7(AIN1)-Pad11)") (class "Default")
      (node (ref "IC1") (pin "11") (pinfunction "PD7(AIN1)_11") (pintype "bidirectional"))
    )
  )
)
